# MAX3738ETG_MEZ.net
KiCad netlist of a schematic drawn in Altium Designer
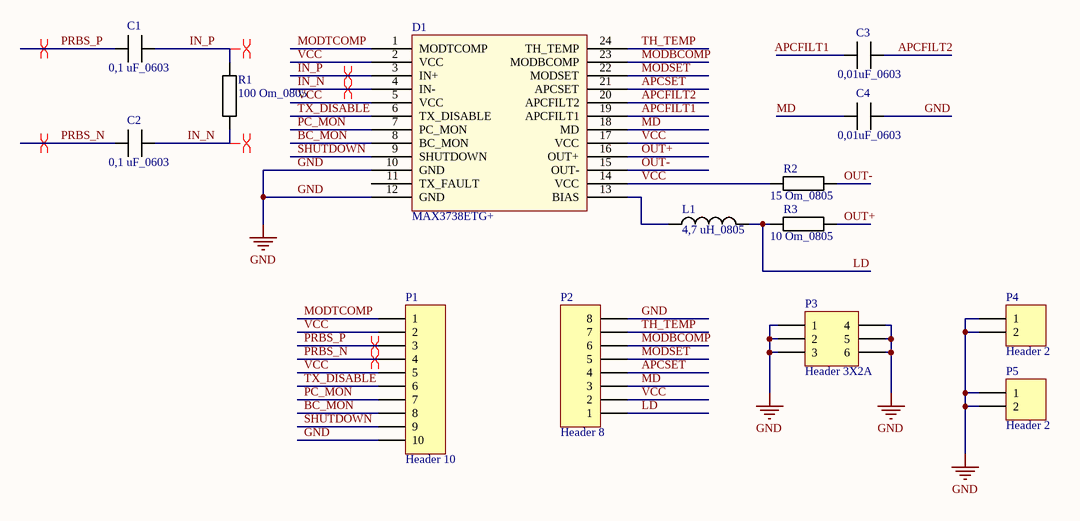
[diagram p0: MAX3738ETG+ MEZ.SchDoc]

(export (version "E")
  (design (tool "Eeschema 10.0.6"))
  (components
    (comp (ref "C1")
      (value "0,1 uF_0603")
      (footprint "aab_Passive:CAP_0603")
      (libsource (lib "aab_Schlib") (part "CAP"))
    )
    (comp (ref "C2")
      (value "0,1 uF_0603")
      (footprint "aab_Passive:CAP_0603")
      (libsource (lib "aab_Schlib") (part "CAP"))
    )
    (comp (ref "C3")
      (value "0,01uF_0603")
      (footprint "aab_Passive:CAP_0603")
      (libsource (lib "aab_Schlib") (part "CAP"))
    )
    (comp (ref "C4")
      (value "0,01uF_0603")
      (footprint "aab_Passive:CAP_0603")
      (libsource (lib "aab_Schlib") (part "CAP"))
    )
    (comp (ref "D1")
      (value "MAX3738ETG+")
      (footprint "aab_Active:MAX3738ETG+")
      (libsource (lib "aab_Schlib") (part "MAX3738ETG+"))
    )
    (comp (ref "L1")
      (value "4,7 uH_0805")
      (footprint "aab_Passive:IND_0805")
      (libsource (lib "aab_Schlib") (part "IND"))
    )
    (comp (ref "P1")
      (value "Header 10")
      (footprint "HDR1X10")
      (description "Header, 10-Pin")
      (fields (field (name "PUBLISHER") "Altium Limited"))
      (libsource (lib "Miscellaneous Connectors") (part "Header 10"))
    )
    (comp (ref "P2")
      (value "Header 8")
      (footprint "HDR1X8")
      (description "Header, 8-Pin")
      (fields (field (name "PUBLISHER") "Altium Limited"))
      (libsource (lib "Miscellaneous Connectors") (part "Header 8"))
    )
    (comp (ref "P3")
      (value "Header 3X2A")
      (footprint "HDR2X3_CEN")
      (description "Header, 3-Pin, Dual row")
      (fields (field (name "PUBLISHER") "Altium Limited"))
      (libsource (lib "Miscellaneous Connectors") (part "Header 3X2A"))
    )
    (comp (ref "P4")
      (value "Header 2")
      (footprint "HDR1X2")
      (description "Header, 2-Pin")
      (fields (field (name "PUBLISHER") "Altium Limited"))
      (libsource (lib "Miscellaneous Connectors") (part "Header 2"))
    )
    (comp (ref "P5")
      (value "Header 2")
      (footprint "HDR1X2")
      (description "Header, 2-Pin")
      (fields (field (name "PUBLISHER") "Altium Limited"))
      (libsource (lib "Miscellaneous Connectors") (part "Header 2"))
    )
    (comp (ref "R1")
      (value "100 Om_0805")
      (footprint "aab_Passive:RES_0805")
      (libsource (lib "aab_Schlib") (part "RES"))
    )
    (comp (ref "R2")
      (value "15 Om_0805")
      (footprint "aab_Passive:RES_0805")
      (libsource (lib "aab_Schlib") (part "RES"))
    )
    (comp (ref "R3")
      (value "10 Om_0805")
      (footprint "aab_Passive:RES_0805")
      (libsource (lib "aab_Schlib") (part "RES"))
    )
  )
  (nets
    (net (code "1") (name "/APCFILT1") (class "Default")
      (node (ref "C3") (pin "1") (pinfunction "1_1") (pintype "passive"))
      (node (ref "D1") (pin "19") (pinfunction "APCFILT1_19") (pintype "passive"))
    )
    (net (code "2") (name "/APCFILT2") (class "Default")
      (node (ref "C3") (pin "2") (pinfunction "2_2") (pintype "passive"))
      (node (ref "D1") (pin "20") (pinfunction "APCFILT2_20") (pintype "passive"))
    )
    (net (code "3") (name "/APCSET") (class "Default")
      (node (ref "D1") (pin "21") (pinfunction "APCSET_21") (pintype "passive"))
      (node (ref "P2") (pin "4") (pinfunction "4_4") (pintype "passive"))
    )
    (net (code "4") (name "/BC_MON") (class "Default")
      (node (ref "D1") (pin "8") (pinfunction "BC_MON_8") (pintype "passive"))
      (node (ref "P1") (pin "8") (pinfunction "8_8") (pintype "passive"))
    )
    (net (code "5") (name "/IN_N") (class "Default")
      (node (ref "C2") (pin "2") (pinfunction "2_2") (pintype "passive"))
      (node (ref "D1") (pin "4") (pinfunction "IN-_4") (pintype "passive"))
      (node (ref "R1") (pin "1") (pinfunction "1_1") (pintype "passive"))
    )
    (net (code "6") (name "/IN_P") (class "Default")
      (node (ref "C1") (pin "2") (pinfunction "2_2") (pintype "passive"))
      (node (ref "D1") (pin "3") (pinfunction "IN+_3") (pintype "passive"))
      (node (ref "R1") (pin "2") (pinfunction "2_2") (pintype "passive"))
    )
    (net (code "7") (name "/LD") (class "Default")
      (node (ref "L1") (pin "2") (pinfunction "2_2") (pintype "passive"))
      (node (ref "P2") (pin "1") (pinfunction "1_1") (pintype "passive"))
      (node (ref "R3") (pin "1") (pinfunction "1_1") (pintype "passive"))
    )
    (net (code "8") (name "/MD") (class "Default")
      (node (ref "C4") (pin "1") (pinfunction "1_1") (pintype "passive"))
      (node (ref "D1") (pin "18") (pinfunction "MD_18") (pintype "passive"))
      (node (ref "P2") (pin "3") (pinfunction "3_3") (pintype "passive"))
    )
    (net (code "9") (name "/MODBCOMP") (class "Default")
      (node (ref "D1") (pin "23") (pinfunction "MODBCOMP_23") (pintype "passive"))
      (node (ref "P2") (pin "6") (pinfunction "6_6") (pintype "passive"))
    )
    (net (code "10") (name "/MODSET") (class "Default")
      (node (ref "D1") (pin "22") (pinfunction "MODSET_22") (pintype "passive"))
      (node (ref "P2") (pin "5") (pinfunction "5_5") (pintype "passive"))
    )
    (net (code "11") (name "/MODTCOMP") (class "Default")
      (node (ref "D1") (pin "1") (pinfunction "MODTCOMP_1") (pintype "passive"))
      (node (ref "P1") (pin "1") (pinfunction "1_1") (pintype "passive"))
    )
    (net (code "12") (name "/OUT+") (class "Default")
      (node (ref "D1") (pin "16") (pinfunction "OUT+_16") (pintype "passive"))
      (node (ref "R3") (pin "2") (pinfunction "2_2") (pintype "passive"))
    )
    (net (code "13") (name "/OUT-") (class "Default")
      (node (ref "D1") (pin "15") (pinfunction "OUT-_15") (pintype "passive"))
      (node (ref "R2") (pin "2") (pinfunction "2_2") (pintype "passive"))
    )
    (net (code "14") (name "/PC_MON") (class "Default")
      (node (ref "D1") (pin "7") (pinfunction "PC_MON_7") (pintype "passive"))
      (node (ref "P1") (pin "7") (pinfunction "7_7") (pintype "passive"))
    )
    (net (code "15") (name "/PRBS_N") (class "Default")
      (node (ref "C2") (pin "1") (pinfunction "1_1") (pintype "passive"))
      (node (ref "P1") (pin "4") (pinfunction "4_4") (pintype "passive"))
    )
    (net (code "16") (name "/PRBS_P") (class "Default")
      (node (ref "C1") (pin "1") (pinfunction "1_1") (pintype "passive"))
      (node (ref "P1") (pin "3") (pinfunction "3_3") (pintype "passive"))
    )
    (net (code "17") (name "/SHUTDOWN") (class "Default")
      (node (ref "D1") (pin "9") (pinfunction "SHUTDOWN_9") (pintype "passive"))
      (node (ref "P1") (pin "9") (pinfunction "9_9") (pintype "passive"))
    )
    (net (code "18") (name "/TH_TEMP") (class "Default")
      (node (ref "D1") (pin "24") (pinfunction "TH_TEMP_24") (pintype "passive"))
      (node (ref "P2") (pin "7") (pinfunction "7_7") (pintype "passive"))
    )
    (net (code "19") (name "/TX_DISABLE") (class "Default")
      (node (ref "D1") (pin "6") (pinfunction "TX_DISABLE_6") (pintype "passive"))
      (node (ref "P1") (pin "6") (pinfunction "6_6") (pintype "passive"))
    )
    (net (code "20") (name "/VCC") (class "Default")
      (node (ref "D1") (pin "14") (pinfunction "VCC_14") (pintype "passive"))
      (node (ref "D1") (pin "17") (pinfunction "VCC_17") (pintype "passive"))
      (node (ref "D1") (pin "2") (pinfunction "VCC_2") (pintype "passive"))
      (node (ref "D1") (pin "5") (pinfunction "VCC_5") (pintype "passive"))
      (node (ref "P1") (pin "2") (pinfunction "2_2") (pintype "passive"))
      (node (ref "P1") (pin "5") (pinfunction "5_5") (pintype "passive"))
      (node (ref "P2") (pin "2") (pinfunction "2_2") (pintype "passive"))
      (node (ref "R2") (pin "1") (pinfunction "1_1") (pintype "passive"))
    )
    (net (code "21") (name "GND") (class "Default")
      (node (ref "C4") (pin "2") (pinfunction "2_2") (pintype "passive"))
      (node (ref "D1") (pin "10") (pinfunction "GND_10") (pintype "passive"))
      (node (ref "D1") (pin "12") (pinfunction "GND_12") (pintype "passive"))
      (node (ref "P1") (pin "10") (pinfunction "10_10") (pintype "passive"))
      (node (ref "P2") (pin "8") (pinfunction "8_8") (pintype "passive"))
      (node (ref "P3") (pin "1") (pinfunction "1_1") (pintype "passive"))
      (node (ref "P3") (pin "2") (pinfunction "2_2") (pintype "passive"))
      (node (ref "P3") (pin "3") (pinfunction "3_3") (pintype "passive"))
      (node (ref "P3") (pin "4") (pinfunction "4_4") (pintype "passive"))
      (node (ref "P3") (pin "5") (pinfunction "5_5") (pintype "passive"))
      (node (ref "P3") (pin "6") (pinfunction "6_6") (pintype "passive"))
      (node (ref "P4") (pin "1") (pinfunction "1_1") (pintype "passive"))
      (node (ref "P4") (pin "2") (pinfunction "2_2") (pintype "passive"))
      (node (ref "P5") (pin "1") (pinfunction "1_1") (pintype "passive"))
      (node (ref "P5") (pin "2") (pinfunction "2_2") (pintype "passive"))
    )
    (net (code "22") (name "Net-(D1-BIAS)") (class "Default")
      (node (ref "D1") (pin "13") (pinfunction "BIAS_13") (pintype "passive"))
      (node (ref "L1") (pin "1") (pinfunction "1_1") (pintype "passive"))
    )
    (net (code "23") (name "unconnected-(D1-TX_FAULT-Pad11)") (class "Default")
      (node (ref "D1") (pin "11") (pinfunction "TX_FAULT_11") (pintype "passive"))
    )
  )
)
